# Quad_VCA_MAIN_v1.net
KiCad netlist of a schematic drawn in EAGLE
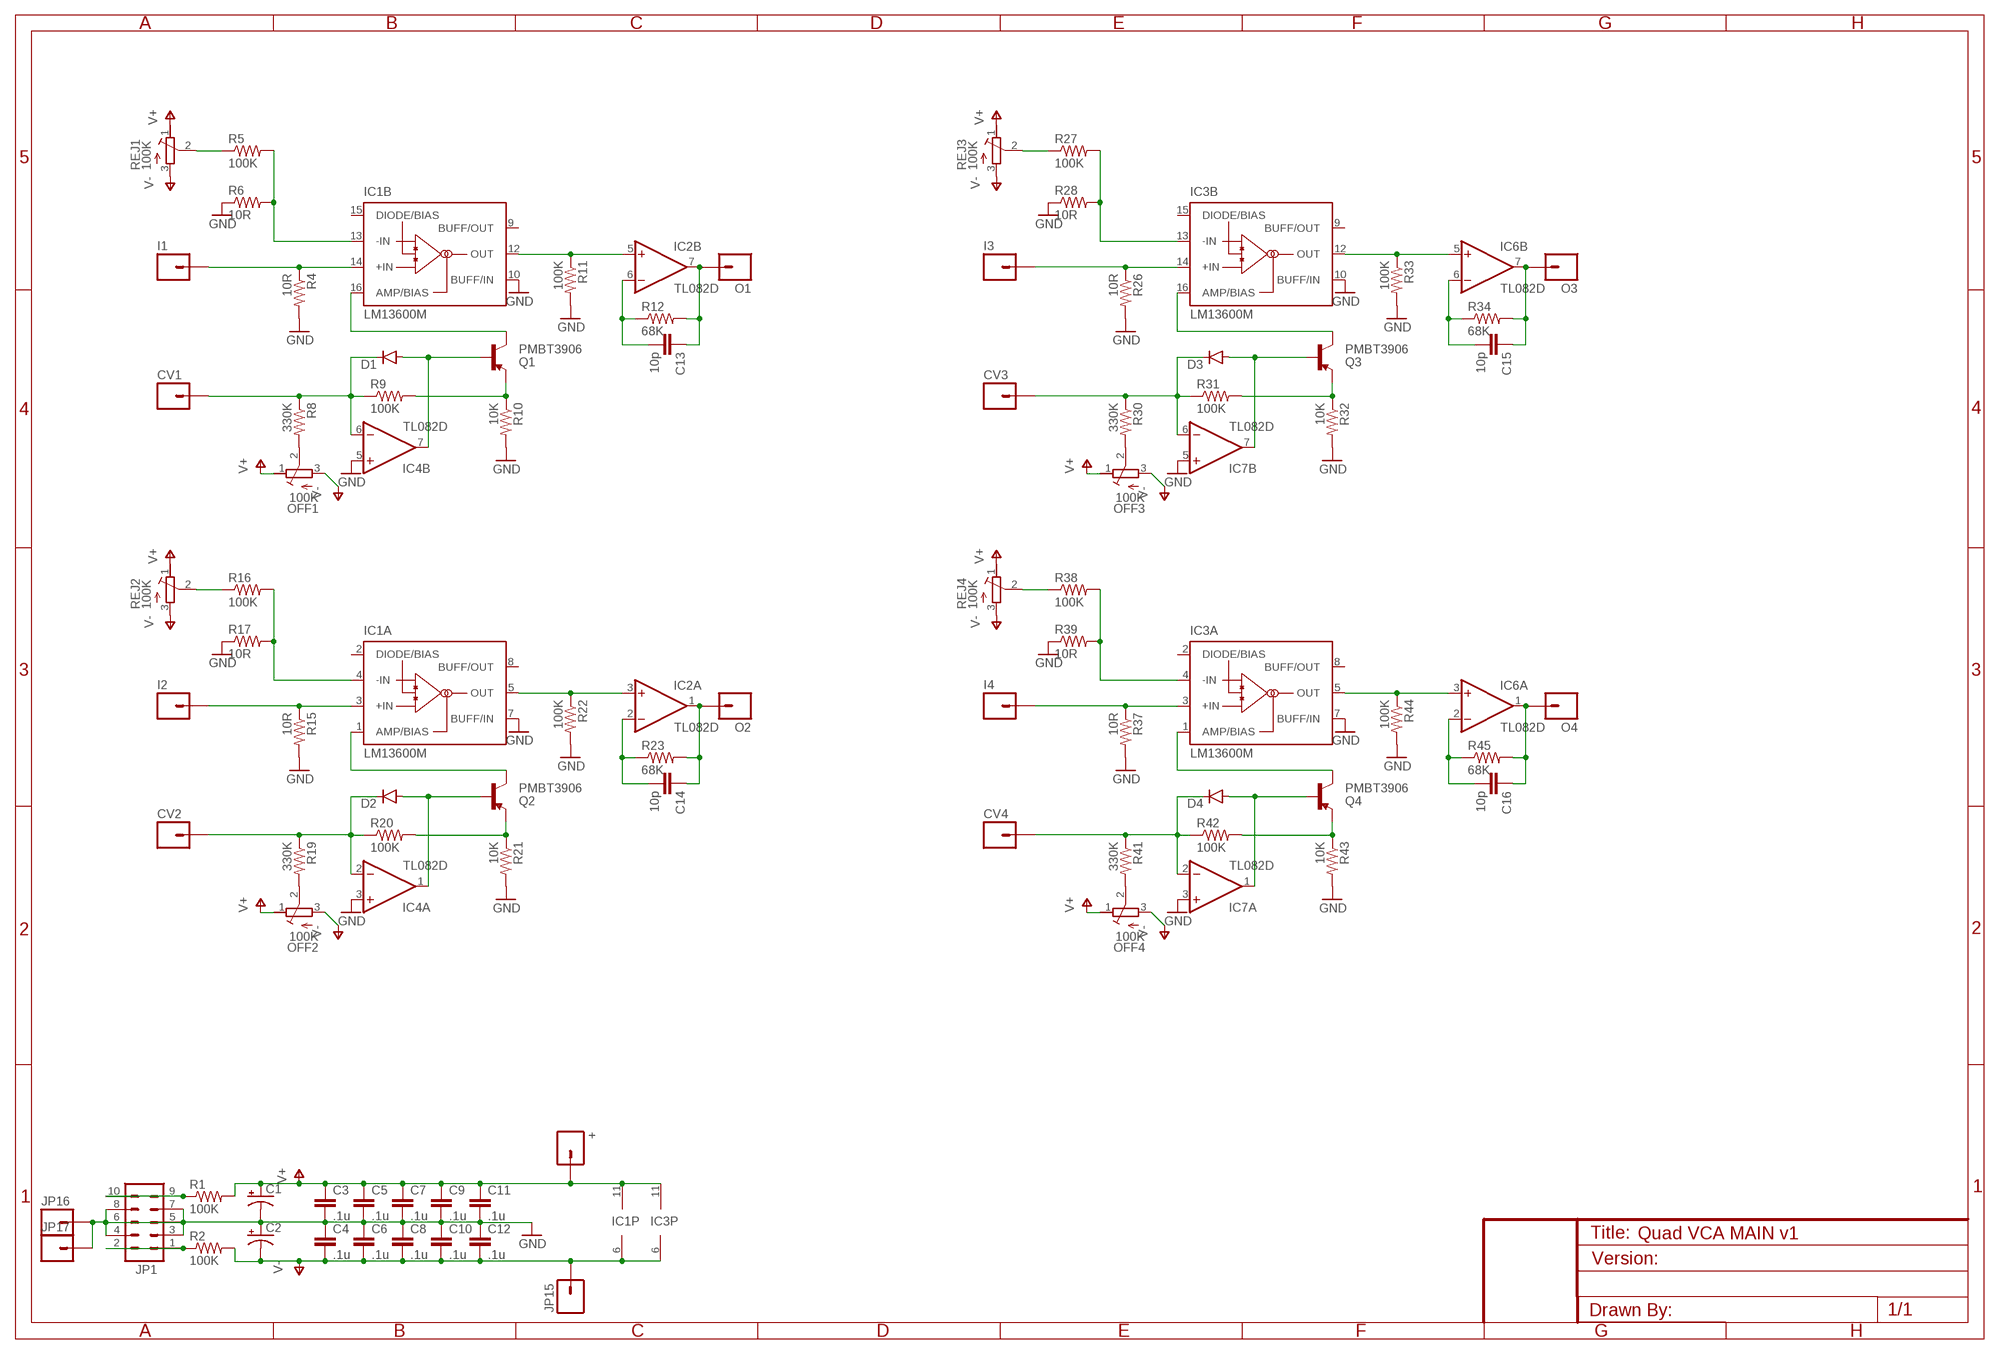
[diagram p0: schematic, sheet 1]

(export (version "E")
  (design (tool "Eeschema 10.0.6"))
  (components
    (comp (ref "+")
      (value "M01PTH")
      (footprint "eagle-import:1X01")
      (libsource (lib "eagle-import") (part "M01PTH"))
    )
    (comp (ref "C1")
      (value "CAP_POLPTH2")
      (footprint "eagle-import:CPOL-RADIAL-10UF-25V")
      (libsource (lib "eagle-import") (part "CAP_POLPTH2"))
    )
    (comp (ref "C2")
      (value "CAP_POLPTH2")
      (footprint "eagle-import:CPOL-RADIAL-10UF-25V")
      (libsource (lib "eagle-import") (part "CAP_POLPTH2"))
    )
    (comp (ref "C3")
      (value ".1u")
      (footprint "eagle-import:0805")
      (libsource (lib "eagle-import") (part "CAP0805"))
    )
    (comp (ref "C4")
      (value ".1u")
      (footprint "eagle-import:0805")
      (libsource (lib "eagle-import") (part "CAP0805"))
    )
    (comp (ref "C5")
      (value ".1u")
      (footprint "eagle-import:0805")
      (libsource (lib "eagle-import") (part "CAP0805"))
    )
    (comp (ref "C6")
      (value ".1u")
      (footprint "eagle-import:0805")
      (libsource (lib "eagle-import") (part "CAP0805"))
    )
    (comp (ref "C7")
      (value ".1u")
      (footprint "eagle-import:0805")
      (libsource (lib "eagle-import") (part "CAP0805"))
    )
    (comp (ref "C8")
      (value ".1u")
      (footprint "eagle-import:0805")
      (libsource (lib "eagle-import") (part "CAP0805"))
    )
    (comp (ref "C9")
      (value ".1u")
      (footprint "eagle-import:0805")
      (libsource (lib "eagle-import") (part "CAP0805"))
    )
    (comp (ref "C10")
      (value ".1u")
      (footprint "eagle-import:0805")
      (libsource (lib "eagle-import") (part "CAP0805"))
    )
    (comp (ref "C11")
      (value ".1u")
      (footprint "eagle-import:0805")
      (libsource (lib "eagle-import") (part "CAP0805"))
    )
    (comp (ref "C12")
      (value ".1u")
      (footprint "eagle-import:0805")
      (libsource (lib "eagle-import") (part "CAP0805"))
    )
    (comp (ref "C13")
      (value "10p")
      (footprint "eagle-import:0805")
      (libsource (lib "eagle-import") (part "CAP0805"))
    )
    (comp (ref "C14")
      (value "10p")
      (footprint "eagle-import:0805")
      (libsource (lib "eagle-import") (part "CAP0805"))
    )
    (comp (ref "C15")
      (value "10p")
      (footprint "eagle-import:0805")
      (libsource (lib "eagle-import") (part "CAP0805"))
    )
    (comp (ref "C16")
      (value "10p")
      (footprint "eagle-import:0805")
      (libsource (lib "eagle-import") (part "CAP0805"))
    )
    (comp (ref "CV1")
      (value "M01PTH")
      (footprint "eagle-import:1X01")
      (libsource (lib "eagle-import") (part "M01PTH"))
    )
    (comp (ref "CV2")
      (value "M01PTH")
      (footprint "eagle-import:1X01")
      (libsource (lib "eagle-import") (part "M01PTH"))
    )
    (comp (ref "CV3")
      (value "M01PTH")
      (footprint "eagle-import:1X01")
      (libsource (lib "eagle-import") (part "M01PTH"))
    )
    (comp (ref "CV4")
      (value "M01PTH")
      (footprint "eagle-import:1X01")
      (libsource (lib "eagle-import") (part "M01PTH"))
    )
    (comp (ref "D1")
      (value "DIODESOD123")
      (footprint "eagle-import:SOD-123")
      (libsource (lib "eagle-import") (part "DIODESOD123"))
    )
    (comp (ref "D2")
      (value "DIODESOD123")
      (footprint "eagle-import:SOD-123")
      (libsource (lib "eagle-import") (part "DIODESOD123"))
    )
    (comp (ref "D3")
      (value "DIODESOD123")
      (footprint "eagle-import:SOD-123")
      (libsource (lib "eagle-import") (part "DIODESOD123"))
    )
    (comp (ref "D4")
      (value "DIODESOD123")
      (footprint "eagle-import:SOD-123")
      (libsource (lib "eagle-import") (part "DIODESOD123"))
    )
    (comp (ref "I1")
      (value "M01PTH")
      (footprint "eagle-import:1X01")
      (libsource (lib "eagle-import") (part "M01PTH"))
    )
    (comp (ref "I2")
      (value "M01PTH")
      (footprint "eagle-import:1X01")
      (libsource (lib "eagle-import") (part "M01PTH"))
    )
    (comp (ref "I3")
      (value "M01PTH")
      (footprint "eagle-import:1X01")
      (libsource (lib "eagle-import") (part "M01PTH"))
    )
    (comp (ref "I4")
      (value "M01PTH")
      (footprint "eagle-import:1X01")
      (libsource (lib "eagle-import") (part "M01PTH"))
    )
    (comp (ref "IC1")
      (value "LM13600M")
      (footprint "eagle-import:SO16")
      (libsource (lib "eagle-import") (part "LM13600M"))
    )
    (comp (ref "IC2")
      (value "TL082D")
      (footprint "eagle-import:SO08")
      (libsource (lib "eagle-import") (part "TL082D"))
    )
    (comp (ref "IC3")
      (value "LM13600M")
      (footprint "eagle-import:SO16")
      (libsource (lib "eagle-import") (part "LM13600M"))
    )
    (comp (ref "IC4")
      (value "TL082D")
      (footprint "eagle-import:SO08")
      (libsource (lib "eagle-import") (part "TL082D"))
    )
    (comp (ref "IC6")
      (value "TL082D")
      (footprint "eagle-import:SO08")
      (libsource (lib "eagle-import") (part "TL082D"))
    )
    (comp (ref "IC7")
      (value "TL082D")
      (footprint "eagle-import:SO08")
      (libsource (lib "eagle-import") (part "TL082D"))
    )
    (comp (ref "JP1")
      (value "M05X2PTH")
      (footprint "eagle-import:AVR_ICSP")
      (libsource (lib "eagle-import") (part "M05X2PTH"))
    )
    (comp (ref "JP15")
      (value "M01PTH")
      (footprint "eagle-import:1X01")
      (libsource (lib "eagle-import") (part "M01PTH"))
    )
    (comp (ref "JP16")
      (value "M01PTH")
      (footprint "eagle-import:1X01")
      (libsource (lib "eagle-import") (part "M01PTH"))
    )
    (comp (ref "JP17")
      (value "M01PTH")
      (footprint "eagle-import:1X01")
      (libsource (lib "eagle-import") (part "M01PTH"))
    )
    (comp (ref "O1")
      (value "M01PTH")
      (footprint "eagle-import:1X01")
      (libsource (lib "eagle-import") (part "M01PTH"))
    )
    (comp (ref "O2")
      (value "M01PTH")
      (footprint "eagle-import:1X01")
      (libsource (lib "eagle-import") (part "M01PTH"))
    )
    (comp (ref "O3")
      (value "M01PTH")
      (footprint "eagle-import:1X01")
      (libsource (lib "eagle-import") (part "M01PTH"))
    )
    (comp (ref "O4")
      (value "M01PTH")
      (footprint "eagle-import:1X01")
      (libsource (lib "eagle-import") (part "M01PTH"))
    )
    (comp (ref "OFF1")
      (value "100K")
      (footprint "eagle-import:RTRIM3314G")
      (libsource (lib "eagle-import") (part "R-TRIMM3314G"))
    )
    (comp (ref "OFF2")
      (value "100K")
      (footprint "eagle-import:RTRIM3314G")
      (libsource (lib "eagle-import") (part "R-TRIMM3314G"))
    )
    (comp (ref "OFF3")
      (value "100K")
      (footprint "eagle-import:RTRIM3314G")
      (libsource (lib "eagle-import") (part "R-TRIMM3314G"))
    )
    (comp (ref "OFF4")
      (value "100K")
      (footprint "eagle-import:RTRIM3314G")
      (libsource (lib "eagle-import") (part "R-TRIMM3314G"))
    )
    (comp (ref "Q1")
      (value "PMBT3906")
      (footprint "eagle-import:SOT23-3")
      (libsource (lib "eagle-import") (part "TRANSISTOR_PNPPMBT3906"))
    )
    (comp (ref "Q2")
      (value "PMBT3906")
      (footprint "eagle-import:SOT23-3")
      (libsource (lib "eagle-import") (part "TRANSISTOR_PNPPMBT3906"))
    )
    (comp (ref "Q3")
      (value "PMBT3906")
      (footprint "eagle-import:SOT23-3")
      (libsource (lib "eagle-import") (part "TRANSISTOR_PNPPMBT3906"))
    )
    (comp (ref "Q4")
      (value "PMBT3906")
      (footprint "eagle-import:SOT23-3")
      (libsource (lib "eagle-import") (part "TRANSISTOR_PNPPMBT3906"))
    )
    (comp (ref "R1")
      (value "100K")
      (footprint "eagle-import:0805")
      (libsource (lib "eagle-import") (part "RESISTOR0805-RES"))
    )
    (comp (ref "R2")
      (value "100K")
      (footprint "eagle-import:0805")
      (libsource (lib "eagle-import") (part "RESISTOR0805-RES"))
    )
    (comp (ref "R4")
      (value "10R")
      (footprint "eagle-import:0805")
      (libsource (lib "eagle-import") (part "RESISTOR0805-RES"))
    )
    (comp (ref "R5")
      (value "100K")
      (footprint "eagle-import:0805")
      (libsource (lib "eagle-import") (part "RESISTOR0805-RES"))
    )
    (comp (ref "R6")
      (value "10R")
      (footprint "eagle-import:0805")
      (libsource (lib "eagle-import") (part "RESISTOR0805-RES"))
    )
    (comp (ref "R8")
      (value "330K")
      (footprint "eagle-import:0805")
      (libsource (lib "eagle-import") (part "RESISTOR0805-RES"))
    )
    (comp (ref "R9")
      (value "100K")
      (footprint "eagle-import:0805")
      (libsource (lib "eagle-import") (part "RESISTOR0805-RES"))
    )
    (comp (ref "R10")
      (value "10K")
      (footprint "eagle-import:0805")
      (libsource (lib "eagle-import") (part "RESISTOR0805-RES"))
    )
    (comp (ref "R11")
      (value "100K")
      (footprint "eagle-import:0805")
      (libsource (lib "eagle-import") (part "RESISTOR0805-RES"))
    )
    (comp (ref "R12")
      (value "68K")
      (footprint "eagle-import:0805")
      (libsource (lib "eagle-import") (part "RESISTOR0805-RES"))
    )
    (comp (ref "R15")
      (value "10R")
      (footprint "eagle-import:0805")
      (libsource (lib "eagle-import") (part "RESISTOR0805-RES"))
    )
    (comp (ref "R16")
      (value "100K")
      (footprint "eagle-import:0805")
      (libsource (lib "eagle-import") (part "RESISTOR0805-RES"))
    )
    (comp (ref "R17")
      (value "10R")
      (footprint "eagle-import:0805")
      (libsource (lib "eagle-import") (part "RESISTOR0805-RES"))
    )
    (comp (ref "R19")
      (value "330K")
      (footprint "eagle-import:0805")
      (libsource (lib "eagle-import") (part "RESISTOR0805-RES"))
    )
    (comp (ref "R20")
      (value "100K")
      (footprint "eagle-import:0805")
      (libsource (lib "eagle-import") (part "RESISTOR0805-RES"))
    )
    (comp (ref "R21")
      (value "10K")
      (footprint "eagle-import:0805")
      (libsource (lib "eagle-import") (part "RESISTOR0805-RES"))
    )
    (comp (ref "R22")
      (value "100K")
      (footprint "eagle-import:0805")
      (libsource (lib "eagle-import") (part "RESISTOR0805-RES"))
    )
    (comp (ref "R23")
      (value "68K")
      (footprint "eagle-import:0805")
      (libsource (lib "eagle-import") (part "RESISTOR0805-RES"))
    )
    (comp (ref "R26")
      (value "10R")
      (footprint "eagle-import:0805")
      (libsource (lib "eagle-import") (part "RESISTOR0805-RES"))
    )
    (comp (ref "R27")
      (value "100K")
      (footprint "eagle-import:0805")
      (libsource (lib "eagle-import") (part "RESISTOR0805-RES"))
    )
    (comp (ref "R28")
      (value "10R")
      (footprint "eagle-import:0805")
      (libsource (lib "eagle-import") (part "RESISTOR0805-RES"))
    )
    (comp (ref "R30")
      (value "330K")
      (footprint "eagle-import:0805")
      (libsource (lib "eagle-import") (part "RESISTOR0805-RES"))
    )
    (comp (ref "R31")
      (value "100K")
      (footprint "eagle-import:0805")
      (libsource (lib "eagle-import") (part "RESISTOR0805-RES"))
    )
    (comp (ref "R32")
      (value "10K")
      (footprint "eagle-import:0805")
      (libsource (lib "eagle-import") (part "RESISTOR0805-RES"))
    )
    (comp (ref "R33")
      (value "100K")
      (footprint "eagle-import:0805")
      (libsource (lib "eagle-import") (part "RESISTOR0805-RES"))
    )
    (comp (ref "R34")
      (value "68K")
      (footprint "eagle-import:0805")
      (libsource (lib "eagle-import") (part "RESISTOR0805-RES"))
    )
    (comp (ref "R37")
      (value "10R")
      (footprint "eagle-import:0805")
      (libsource (lib "eagle-import") (part "RESISTOR0805-RES"))
    )
    (comp (ref "R38")
      (value "100K")
      (footprint "eagle-import:0805")
      (libsource (lib "eagle-import") (part "RESISTOR0805-RES"))
    )
    (comp (ref "R39")
      (value "10R")
      (footprint "eagle-import:0805")
      (libsource (lib "eagle-import") (part "RESISTOR0805-RES"))
    )
    (comp (ref "R41")
      (value "330K")
      (footprint "eagle-import:0805")
      (libsource (lib "eagle-import") (part "RESISTOR0805-RES"))
    )
    (comp (ref "R42")
      (value "100K")
      (footprint "eagle-import:0805")
      (libsource (lib "eagle-import") (part "RESISTOR0805-RES"))
    )
    (comp (ref "R43")
      (value "10K")
      (footprint "eagle-import:0805")
      (libsource (lib "eagle-import") (part "RESISTOR0805-RES"))
    )
    (comp (ref "R44")
      (value "100K")
      (footprint "eagle-import:0805")
      (libsource (lib "eagle-import") (part "RESISTOR0805-RES"))
    )
    (comp (ref "R45")
      (value "68K")
      (footprint "eagle-import:0805")
      (libsource (lib "eagle-import") (part "RESISTOR0805-RES"))
    )
    (comp (ref "REJ1")
      (value "100K")
      (footprint "eagle-import:RTRIM3314G")
      (libsource (lib "eagle-import") (part "R-TRIMM3314G"))
    )
    (comp (ref "REJ2")
      (value "100K")
      (footprint "eagle-import:RTRIM3314G")
      (libsource (lib "eagle-import") (part "R-TRIMM3314G"))
    )
    (comp (ref "REJ3")
      (value "100K")
      (footprint "eagle-import:RTRIM3314G")
      (libsource (lib "eagle-import") (part "R-TRIMM3314G"))
    )
    (comp (ref "REJ4")
      (value "100K")
      (footprint "eagle-import:RTRIM3314G")
      (libsource (lib "eagle-import") (part "R-TRIMM3314G"))
    )
  )
  (nets
    (net (code "1") (name "GND") (class "Default")
      (node (ref "C1") (pin "2") (pinfunction "-_2") (pintype "passive"))
      (node (ref "C10") (pin "1") (pinfunction "1_1") (pintype "passive"))
      (node (ref "C11") (pin "2") (pinfunction "2_2") (pintype "passive"))
      (node (ref "C12") (pin "1") (pinfunction "1_1") (pintype "passive"))
      (node (ref "C2") (pin "1") (pinfunction "+_1") (pintype "passive"))
      (node (ref "C3") (pin "2") (pinfunction "2_2") (pintype "passive"))
      (node (ref "C4") (pin "1") (pinfunction "1_1") (pintype "passive"))
      (node (ref "C5") (pin "2") (pinfunction "2_2") (pintype "passive"))
      (node (ref "C6") (pin "1") (pinfunction "1_1") (pintype "passive"))
      (node (ref "C7") (pin "2") (pinfunction "2_2") (pintype "passive"))
      (node (ref "C8") (pin "1") (pinfunction "1_1") (pintype "passive"))
      (node (ref "C9") (pin "2") (pinfunction "2_2") (pintype "passive"))
      (node (ref "IC1") (pin "10") (pinfunction "BUFF/IN_10") (pintype "input"))
      (node (ref "IC1") (pin "7") (pinfunction "BUFF/IN_7") (pintype "input"))
      (node (ref "IC3") (pin "10") (pinfunction "BUFF/IN_10") (pintype "input"))
      (node (ref "IC3") (pin "7") (pinfunction "BUFF/IN_7") (pintype "input"))
      (node (ref "IC4") (pin "3") (pinfunction "+IN_3") (pintype "input"))
      (node (ref "IC4") (pin "5") (pinfunction "+IN_5") (pintype "input"))
      (node (ref "IC7") (pin "3") (pinfunction "+IN_3") (pintype "input"))
      (node (ref "IC7") (pin "5") (pinfunction "+IN_5") (pintype "input"))
      (node (ref "JP1") (pin "3") (pinfunction "3_3") (pintype "passive"))
      (node (ref "JP1") (pin "4") (pinfunction "4_4") (pintype "passive"))
      (node (ref "JP1") (pin "5") (pinfunction "5_5") (pintype "passive"))
      (node (ref "JP1") (pin "6") (pinfunction "6_6") (pintype "passive"))
      (node (ref "JP1") (pin "7") (pinfunction "7_7") (pintype "passive"))
      (node (ref "JP1") (pin "8") (pinfunction "8_8") (pintype "passive"))
      (node (ref "JP16") (pin "1") (pinfunction "1_1") (pintype "passive"))
      (node (ref "JP17") (pin "1") (pinfunction "1_1") (pintype "passive"))
      (node (ref "R10") (pin "2") (pinfunction "2_2") (pintype "passive"))
      (node (ref "R11") (pin "2") (pinfunction "2_2") (pintype "passive"))
      (node (ref "R15") (pin "2") (pinfunction "2_2") (pintype "passive"))
      (node (ref "R17") (pin "1") (pinfunction "1_1") (pintype "passive"))
      (node (ref "R21") (pin "2") (pinfunction "2_2") (pintype "passive"))
      (node (ref "R22") (pin "2") (pinfunction "2_2") (pintype "passive"))
      (node (ref "R26") (pin "2") (pinfunction "2_2") (pintype "passive"))
      (node (ref "R28") (pin "1") (pinfunction "1_1") (pintype "passive"))
      (node (ref "R32") (pin "2") (pinfunction "2_2") (pintype "passive"))
      (node (ref "R33") (pin "2") (pinfunction "2_2") (pintype "passive"))
      (node (ref "R37") (pin "2") (pinfunction "2_2") (pintype "passive"))
      (node (ref "R39") (pin "1") (pinfunction "1_1") (pintype "passive"))
      (node (ref "R4") (pin "2") (pinfunction "2_2") (pintype "passive"))
      (node (ref "R43") (pin "2") (pinfunction "2_2") (pintype "passive"))
      (node (ref "R44") (pin "2") (pinfunction "2_2") (pintype "passive"))
      (node (ref "R6") (pin "1") (pinfunction "1_1") (pintype "passive"))
    )
    (net (code "2") (name "Net-(IC1A-+IN)") (class "Default")
      (node (ref "I2") (pin "1") (pinfunction "1_1") (pintype "passive"))
      (node (ref "IC1") (pin "3") (pinfunction "+IN_3") (pintype "input"))
      (node (ref "R15") (pin "1") (pinfunction "1_1") (pintype "passive"))
    )
    (net (code "3") (name "Net-(IC1A--IN)") (class "Default")
      (node (ref "IC1") (pin "4") (pinfunction "-IN_4") (pintype "input"))
      (node (ref "R16") (pin "2") (pinfunction "2_2") (pintype "passive"))
      (node (ref "R17") (pin "2") (pinfunction "2_2") (pintype "passive"))
    )
    (net (code "4") (name "Net-(IC1A-AMP{slash}BIAS)") (class "Default")
      (node (ref "IC1") (pin "1") (pinfunction "AMP/BIAS_1") (pintype "passive"))
      (node (ref "Q2") (pin "3") (pinfunction "C_3") (pintype "passive"))
    )
    (net (code "5") (name "Net-(IC1A-OUT)") (class "Default")
      (node (ref "IC1") (pin "5") (pinfunction "OUT_5") (pintype "output"))
      (node (ref "IC2") (pin "3") (pinfunction "+IN_3") (pintype "input"))
      (node (ref "R22") (pin "1") (pinfunction "1_1") (pintype "passive"))
    )
    (net (code "6") (name "Net-(IC1B-+IN)") (class "Default")
      (node (ref "I1") (pin "1") (pinfunction "1_1") (pintype "passive"))
      (node (ref "IC1") (pin "14") (pinfunction "+IN_14") (pintype "input"))
      (node (ref "R4") (pin "1") (pinfunction "1_1") (pintype "passive"))
    )
    (net (code "7") (name "Net-(IC1B--IN)") (class "Default")
      (node (ref "IC1") (pin "13") (pinfunction "-IN_13") (pintype "input"))
      (node (ref "R5") (pin "2") (pinfunction "2_2") (pintype "passive"))
      (node (ref "R6") (pin "2") (pinfunction "2_2") (pintype "passive"))
    )
    (net (code "8") (name "Net-(IC1B-AMP{slash}BIAS)") (class "Default")
      (node (ref "IC1") (pin "16") (pinfunction "AMP/BIAS_16") (pintype "passive"))
      (node (ref "Q1") (pin "3") (pinfunction "C_3") (pintype "passive"))
    )
    (net (code "9") (name "Net-(IC1B-OUT)") (class "Default")
      (node (ref "IC1") (pin "12") (pinfunction "OUT_12") (pintype "output"))
      (node (ref "IC2") (pin "5") (pinfunction "+IN_5") (pintype "input"))
      (node (ref "R11") (pin "1") (pinfunction "1_1") (pintype "passive"))
    )
    (net (code "10") (name "Net-(IC2A--IN)") (class "Default")
      (node (ref "C14") (pin "2") (pinfunction "2_2") (pintype "passive"))
      (node (ref "IC2") (pin "2") (pinfunction "-IN_2") (pintype "input"))
      (node (ref "R23") (pin "1") (pinfunction "1_1") (pintype "passive"))
    )
    (net (code "11") (name "Net-(IC2A-OUT)") (class "Default")
      (node (ref "C14") (pin "1") (pinfunction "1_1") (pintype "passive"))
      (node (ref "IC2") (pin "1") (pinfunction "OUT_1") (pintype "output"))
      (node (ref "O2") (pin "1") (pinfunction "1_1") (pintype "passive"))
      (node (ref "R23") (pin "2") (pinfunction "2_2") (pintype "passive"))
    )
    (net (code "12") (name "Net-(IC2B--IN)") (class "Default")
      (node (ref "C13") (pin "2") (pinfunction "2_2") (pintype "passive"))
      (node (ref "IC2") (pin "6") (pinfunction "-IN_6") (pintype "input"))
      (node (ref "R12") (pin "1") (pinfunction "1_1") (pintype "passive"))
    )
    (net (code "13") (name "Net-(IC2B-OUT)") (class "Default")
      (node (ref "C13") (pin "1") (pinfunction "1_1") (pintype "passive"))
      (node (ref "IC2") (pin "7") (pinfunction "OUT_7") (pintype "output"))
      (node (ref "O1") (pin "1") (pinfunction "1_1") (pintype "passive"))
      (node (ref "R12") (pin "2") (pinfunction "2_2") (pintype "passive"))
    )
    (net (code "14") (name "Net-(IC3A-+IN)") (class "Default")
      (node (ref "I4") (pin "1") (pinfunction "1_1") (pintype "passive"))
      (node (ref "IC3") (pin "3") (pinfunction "+IN_3") (pintype "input"))
      (node (ref "R37") (pin "1") (pinfunction "1_1") (pintype "passive"))
    )
    (net (code "15") (name "Net-(IC3A--IN)") (class "Default")
      (node (ref "IC3") (pin "4") (pinfunction "-IN_4") (pintype "input"))
      (node (ref "R38") (pin "2") (pinfunction "2_2") (pintype "passive"))
      (node (ref "R39") (pin "2") (pinfunction "2_2") (pintype "passive"))
    )
    (net (code "16") (name "Net-(IC3A-AMP{slash}BIAS)") (class "Default")
      (node (ref "IC3") (pin "1") (pinfunction "AMP/BIAS_1") (pintype "passive"))
      (node (ref "Q4") (pin "3") (pinfunction "C_3") (pintype "passive"))
    )
    (net (code "17") (name "Net-(IC3A-OUT)") (class "Default")
      (node (ref "IC3") (pin "5") (pinfunction "OUT_5") (pintype "output"))
      (node (ref "IC6") (pin "3") (pinfunction "+IN_3") (pintype "input"))
      (node (ref "R44") (pin "1") (pinfunction "1_1") (pintype "passive"))
    )
    (net (code "18") (name "Net-(IC3B-+IN)") (class "Default")
      (node (ref "I3") (pin "1") (pinfunction "1_1") (pintype "passive"))
      (node (ref "IC3") (pin "14") (pinfunction "+IN_14") (pintype "input"))
      (node (ref "R26") (pin "1") (pinfunction "1_1") (pintype "passive"))
    )
    (net (code "19") (name "Net-(IC3B--IN)") (class "Default")
      (node (ref "IC3") (pin "13") (pinfunction "-IN_13") (pintype "input"))
      (node (ref "R27") (pin "2") (pinfunction "2_2") (pintype "passive"))
      (node (ref "R28") (pin "2") (pinfunction "2_2") (pintype "passive"))
    )
    (net (code "20") (name "Net-(IC3B-AMP{slash}BIAS)") (class "Default")
      (node (ref "IC3") (pin "16") (pinfunction "AMP/BIAS_16") (pintype "passive"))
      (node (ref "Q3") (pin "3") (pinfunction "C_3") (pintype "passive"))
    )
    (net (code "21") (name "Net-(IC3B-OUT)") (class "Default")
      (node (ref "IC3") (pin "12") (pinfunction "OUT_12") (pintype "output"))
      (node (ref "IC6") (pin "5") (pinfunction "+IN_5") (pintype "input"))
      (node (ref "R33") (pin "1") (pinfunction "1_1") (pintype "passive"))
    )
    (net (code "22") (name "Net-(IC4A--IN)") (class "Default")
      (node (ref "CV2") (pin "1") (pinfunction "1_1") (pintype "passive"))
      (node (ref "D2") (pin "C") (pinfunction "C_C") (pintype "passive"))
      (node (ref "IC4") (pin "2") (pinfunction "-IN_2") (pintype "input"))
      (node (ref "R19") (pin "1") (pinfunction "1_1") (pintype "passive"))
      (node (ref "R20") (pin "1") (pinfunction "1_1") (pintype "passive"))
    )
    (net (code "23") (name "Net-(IC4A-OUT)") (class "Default")
      (node (ref "D2") (pin "A") (pinfunction "A_A") (pintype "passive"))
      (node (ref "IC4") (pin "1") (pinfunction "OUT_1") (pintype "output"))
      (node (ref "Q2") (pin "1") (pinfunction "B_1") (pintype "passive"))
    )
    (net (code "24") (name "Net-(IC4B--IN)") (class "Default")
      (node (ref "CV1") (pin "1") (pinfunction "1_1") (pintype "passive"))
      (node (ref "D1") (pin "C") (pinfunction "C_C") (pintype "passive"))
      (node (ref "IC4") (pin "6") (pinfunction "-IN_6") (pintype "input"))
      (node (ref "R8") (pin "1") (pinfunction "1_1") (pintype "passive"))
      (node (ref "R9") (pin "1") (pinfunction "1_1") (pintype "passive"))
    )
    (net (code "25") (name "Net-(IC4B-OUT)") (class "Default")
      (node (ref "D1") (pin "A") (pinfunction "A_A") (pintype "passive"))
      (node (ref "IC4") (pin "7") (pinfunction "OUT_7") (pintype "output"))
      (node (ref "Q1") (pin "1") (pinfunction "B_1") (pintype "passive"))
    )
    (net (code "26") (name "Net-(IC6A--IN)") (class "Default")
      (node (ref "C16") (pin "2") (pinfunction "2_2") (pintype "passive"))
      (node (ref "IC6") (pin "2") (pinfunction "-IN_2") (pintype "input"))
      (node (ref "R45") (pin "1") (pinfunction "1_1") (pintype "passive"))
    )
    (net (code "27") (name "Net-(IC6A-OUT)") (class "Default")
      (node (ref "C16") (pin "1") (pinfunction "1_1") (pintype "passive"))
      (node (ref "IC6") (pin "1") (pinfunction "OUT_1") (pintype "output"))
      (node (ref "O4") (pin "1") (pinfunction "1_1") (pintype "passive"))
      (node (ref "R45") (pin "2") (pinfunction "2_2") (pintype "passive"))
    )
    (net (code "28") (name "Net-(IC6B--IN)") (class "Default")
      (node (ref "C15") (pin "2") (pinfunction "2_2") (pintype "passive"))
      (node (ref "IC6") (pin "6") (pinfunction "-IN_6") (pintype "input"))
      (node (ref "R34") (pin "1") (pinfunction "1_1") (pintype "passive"))
    )
    (net (code "29") (name "Net-(IC6B-OUT)") (class "Default")
      (node (ref "C15") (pin "1") (pinfunction "1_1") (pintype "passive"))
      (node (ref "IC6") (pin "7") (pinfunction "OUT_7") (pintype "output"))
      (node (ref "O3") (pin "1") (pinfunction "1_1") (pintype "passive"))
      (node (ref "R34") (pin "2") (pinfunction "2_2") (pintype "passive"))
    )
    (net (code "30") (name "Net-(IC7A--IN)") (class "Default")
      (node (ref "CV4") (pin "1") (pinfunction "1_1") (pintype "passive"))
      (node (ref "D4") (pin "C") (pinfunction "C_C") (pintype "passive"))
      (node (ref "IC7") (pin "2") (pinfunction "-IN_2") (pintype "input"))
      (node (ref "R41") (pin "1") (pinfunction "1_1") (pintype "passive"))
      (node (ref "R42") (pin "1") (pinfunction "1_1") (pintype "passive"))
    )
    (net (code "31") (name "Net-(IC7A-OUT)") (class "Default")
      (node (ref "D4") (pin "A") (pinfunction "A_A") (pintype "passive"))
      (node (ref "IC7") (pin "1") (pinfunction "OUT_1") (pintype "output"))
      (node (ref "Q4") (pin "1") (pinfunction "B_1") (pintype "passive"))
    )
    (net (code "32") (name "Net-(IC7B--IN)") (class "Default")
      (node (ref "CV3") (pin "1") (pinfunction "1_1") (pintype "passive"))
      (node (ref "D3") (pin "C") (pinfunction "C_C") (pintype "passive"))
      (node (ref "IC7") (pin "6") (pinfunction "-IN_6") (pintype "input"))
      (node (ref "R30") (pin "1") (pinfunction "1_1") (pintype "passive"))
      (node (ref "R31") (pin "1") (pinfunction "1_1") (pintype "passive"))
    )
    (net (code "33") (name "Net-(IC7B-OUT)") (class "Default")
      (node (ref "D3") (pin "A") (pinfunction "A_A") (pintype "passive"))
      (node (ref "IC7") (pin "7") (pinfunction "OUT_7") (pintype "output"))
      (node (ref "Q3") (pin "1") (pinfunction "B_1") (pintype "passive"))
    )
    (net (code "34") (name "Net-(JP1-Pad1)") (class "Default")
      (node (ref "JP1") (pin "1") (pinfunction "1_1") (pintype "passive"))
      (node (ref "JP1") (pin "2") (pinfunction "2_2") (pintype "passive"))
      (node (ref "R2") (pin "1") (pinfunction "1_1") (pintype "passive"))
    )
    (net (code "35") (name "Net-(JP1-Pad10)") (class "Default")
      (node (ref "JP1") (pin "10") (pinfunction "10_10") (pintype "passive"))
      (node (ref "JP1") (pin "9") (pinfunction "9_9") (pintype "passive"))
      (node (ref "R1") (pin "1") (pinfunction "1_1") (pintype "passive"))
    )
    (net (code "36") (name "Net-(OFF1-S)") (class "Default")
      (node (ref "OFF1") (pin "2") (pinfunction "S_2") (pintype "passive"))
      (node (ref "R8") (pin "2") (pinfunction "2_2") (pintype "passive"))
    )
    (net (code "37") (name "Net-(OFF2-S)") (class "Default")
      (node (ref "OFF2") (pin "2") (pinfunction "S_2") (pintype "passive"))
      (node (ref "R19") (pin "2") (pinfunction "2_2") (pintype "passive"))
    )
    (net (code "38") (name "Net-(OFF3-S)") (class "Default")
      (node (ref "OFF3") (pin "2") (pinfunction "S_2") (pintype "passive"))
      (node (ref "R30") (pin "2") (pinfunction "2_2") (pintype "passive"))
    )
    (net (code "39") (name "Net-(OFF4-S)") (class "Default")
      (node (ref "OFF4") (pin "2") (pinfunction "S_2") (pintype "passive"))
      (node (ref "R41") (pin "2") (pinfunction "2_2") (pintype "passive"))
    )
    (net (code "40") (name "Net-(Q1-E)") (class "Default")
      (node (ref "Q1") (pin "2") (pinfunction "E_2") (pintype "passive"))
      (node (ref "R10") (pin "1") (pinfunction "1_1") (pintype "passive"))
      (node (ref "R9") (pin "2") (pinfunction "2_2") (pintype "passive"))
    )
    (net (code "41") (name "Net-(Q2-E)") (class "Default")
      (node (ref "Q2") (pin "2") (pinfunction "E_2") (pintype "passive"))
      (node (ref "R20") (pin "2") (pinfunction "2_2") (pintype "passive"))
      (node (ref "R21") (pin "1") (pinfunction "1_1") (pintype "passive"))
    )
    (net (code "42") (name "Net-(Q3-E)") (class "Default")
      (node (ref "Q3") (pin "2") (pinfunction "E_2") (pintype "passive"))
      (node (ref "R31") (pin "2") (pinfunction "2_2") (pintype "passive"))
      (node (ref "R32") (pin "1") (pinfunction "1_1") (pintype "passive"))
    )
    (net (code "43") (name "Net-(Q4-E)") (class "Default")
      (node (ref "Q4") (pin "2") (pinfunction "E_2") (pintype "passive"))
      (node (ref "R42") (pin "2") (pinfunction "2_2") (pintype "passive"))
      (node (ref "R43") (pin "1") (pinfunction "1_1") (pintype "passive"))
    )
    (net (code "44") (name "Net-(REJ1-S)") (class "Default")
      (node (ref "R5") (pin "1") (pinfunction "1_1") (pintype "passive"))
      (node (ref "REJ1") (pin "2") (pinfunction "S_2") (pintype "passive"))
    )
    (net (code "45") (name "Net-(REJ2-S)") (class "Default")
      (node (ref "R16") (pin "1") (pinfunction "1_1") (pintype "passive"))
      (node (ref "REJ2") (pin "2") (pinfunction "S_2") (pintype "passive"))
    )
    (net (code "46") (name "Net-(REJ3-S)") (class "Default")
      (node (ref "R27") (pin "1") (pinfunction "1_1") (pintype "passive"))
      (node (ref "REJ3") (pin "2") (pinfunction "S_2") (pintype "passive"))
    )
    (net (code "47") (name "Net-(REJ4-S)") (class "Default")
      (node (ref "R38") (pin "1") (pinfunction "1_1") (pintype "passive"))
      (node (ref "REJ4") (pin "2") (pinfunction "S_2") (pintype "passive"))
    )
    (net (code "48") (name "V+") (class "Default")
      (node (ref "+") (pin "1") (pinfunction "1_1") (pintype "passive"))
      (node (ref "C1") (pin "1") (pinfunction "+_1") (pintype "passive"))
      (node (ref "C11") (pin "1") (pinfunction "1_1") (pintype "passive"))
      (node (ref "C3") (pin "1") (pinfunction "1_1") (pintype "passive"))
      (node (ref "C5") (pin "1") (pinfunction "1_1") (pintype "passive"))
      (node (ref "C7") (pin "1") (pinfunction "1_1") (pintype "passive"))
      (node (ref "C9") (pin "1") (pinfunction "1_1") (pintype "passive"))
      (node (ref "IC1") (pin "11") (pinfunction "V+_11") (pintype "power_in"))
      (node (ref "IC3") (pin "11") (pinfunction "V+_11") (pintype "power_in"))
      (node (ref "OFF1") (pin "1") (pinfunction "E_1") (pintype "passive"))
      (node (ref "OFF2") (pin "1") (pinfunction "E_1") (pintype "passive"))
      (node (ref "OFF3") (pin "1") (pinfunction "E_1") (pintype "passive"))
      (node (ref "OFF4") (pin "1") (pinfunction "E_1") (pintype "passive"))
      (node (ref "R1") (pin "2") (pinfunction "2_2") (pintype "passive"))
      (node (ref "REJ1") (pin "1") (pinfunction "E_1") (pintype "passive"))
      (node (ref "REJ2") (pin "1") (pinfunction "E_1") (pintype "passive"))
      (node (ref "REJ3") (pin "1") (pinfunction "E_1") (pintype "passive"))
      (node (ref "REJ4") (pin "1") (pinfunction "E_1") (pintype "passive"))
    )
    (net (code "49") (name "V-") (class "Default")
      (node (ref "C10") (pin "2") (pinfunction "2_2") (pintype "passive"))
      (node (ref "C12") (pin "2") (pinfunction "2_2") (pintype "passive"))
      (node (ref "C2") (pin "2") (pinfunction "-_2") (pintype "passive"))
      (node (ref "C4") (pin "2") (pinfunction "2_2") (pintype "passive"))
      (node (ref "C6") (pin "2") (pinfunction "2_2") (pintype "passive"))
      (node (ref "C8") (pin "2") (pinfunction "2_2") (pintype "passive"))
      (node (ref "IC1") (pin "6") (pinfunction "V-_6") (pintype "power_in"))
      (node (ref "IC3") (pin "6") (pinfunction "V-_6") (pintype "power_in"))
      (node (ref "JP15") (pin "1") (pinfunction "1_1") (pintype "passive"))
      (node (ref "OFF1") (pin "3") (pinfunction "A_3") (pintype "passive"))
      (node (ref "OFF2") (pin "3") (pinfunction "A_3") (pintype "passive"))
      (node (ref "OFF3") (pin "3") (pinfunction "A_3") (pintype "passive"))
      (node (ref "OFF4") (pin "3") (pinfunction "A_3") (pintype "passive"))
      (node (ref "R2") (pin "2") (pinfunction "2_2") (pintype "passive"))
      (node (ref "REJ1") (pin "3") (pinfunction "A_3") (pintype "passive"))
      (node (ref "REJ2") (pin "3") (pinfunction "A_3") (pintype "passive"))
      (node (ref "REJ3") (pin "3") (pinfunction "A_3") (pintype "passive"))
      (node (ref "REJ4") (pin "3") (pinfunction "A_3") (pintype "passive"))
    )
    (net (code "50") (name "unconnected-(IC1A-BUFF{slash}OUT-Pad8)") (class "Default")
      (node (ref "IC1") (pin "8") (pinfunction "BUFF/OUT_8") (pintype "output"))
    )
    (net (code "51") (name "unconnected-(IC1A-DIODE{slash}BIAS-Pad2)") (class "Default")
      (node (ref "IC1") (pin "2") (pinfunction "DIODE/BIAS_2") (pintype "passive"))
    )
    (net (code "52") (name "unconnected-(IC1B-BUFF{slash}OUT-Pad9)") (class "Default")
      (node (ref "IC1") (pin "9") (pinfunction "BUFF/OUT_9") (pintype "output"))
    )
    (net (code "53") (name "unconnected-(IC1B-DIODE{slash}BIAS-Pad15)") (class "Default")
      (node (ref "IC1") (pin "15") (pinfunction "DIODE/BIAS_15") (pintype "passive"))
    )
    (net (code "54") (name "unconnected-(IC3A-BUFF{slash}OUT-Pad8)") (class "Default")
      (node (ref "IC3") (pin "8") (pinfunction "BUFF/OUT_8") (pintype "output"))
    )
    (net (code "55") (name "unconnected-(IC3A-DIODE{slash}BIAS-Pad2)") (class "Default")
      (node (ref "IC3") (pin "2") (pinfunction "DIODE/BIAS_2") (pintype "passive"))
    )
    (net (code "56") (name "unconnected-(IC3B-BUFF{slash}OUT-Pad9)") (class "Default")
      (node (ref "IC3") (pin "9") (pinfunction "BUFF/OUT_9") (pintype "output"))
    )
    (net (code "57") (name "unconnected-(IC3B-DIODE{slash}BIAS-Pad15)") (class "Default")
      (node (ref "IC3") (pin "15") (pinfunction "DIODE/BIAS_15") (pintype "passive"))
    )
  )
)
